# CH340BRIDGE_CONVERTER.net
KiCad netlist of a schematic drawn in EAGLE
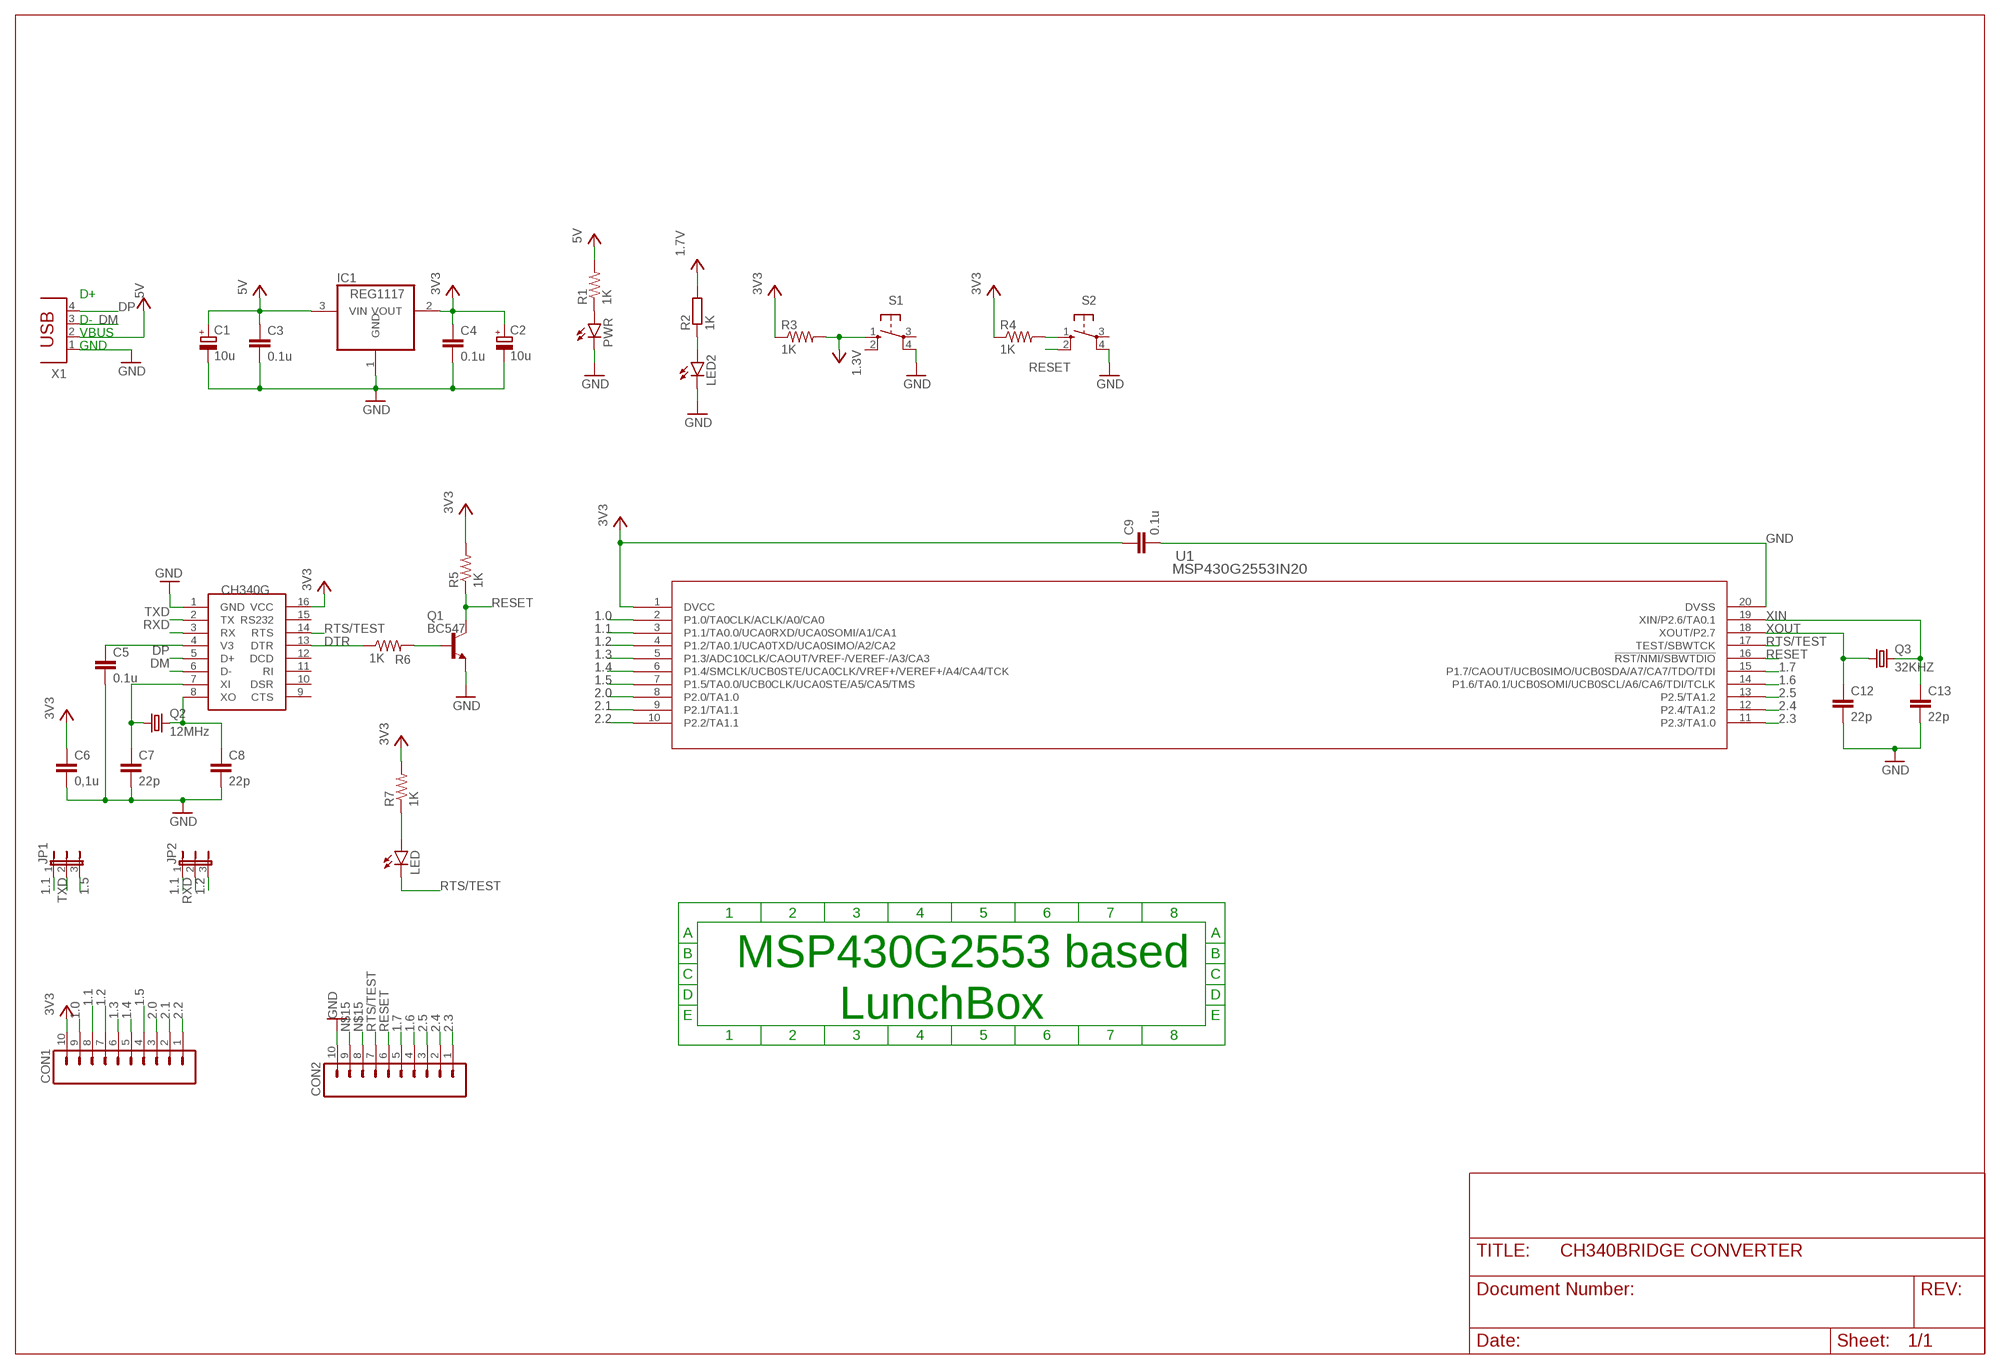
[diagram p0: schematic, sheet 1]

(export (version "E")
  (design (tool "Eeschema 10.0.6"))
  (components
    (comp (ref "C1")
      (value "10u")
      (footprint "eagle-import:TT5D7")
      (libsource (lib "eagle-import") (part "CPOL-EUTT5D7"))
    )
    (comp (ref "C2")
      (value "10u")
      (footprint "eagle-import:TT5D7")
      (libsource (lib "eagle-import") (part "CPOL-EUTT5D7"))
    )
    (comp (ref "C3")
      (value "0.1u")
      (footprint "eagle-import:C025-025X050")
      (libsource (lib "eagle-import") (part "C-EU025-025X050"))
    )
    (comp (ref "C4")
      (value "0.1u")
      (footprint "eagle-import:C025-025X050")
      (libsource (lib "eagle-import") (part "C-EU025-025X050"))
    )
    (comp (ref "C5")
      (value "0.1u")
      (footprint "eagle-import:C0805")
      (libsource (lib "eagle-import") (part "C-EUC0805"))
    )
    (comp (ref "C6")
      (value "0,1u")
      (footprint "eagle-import:C0805")
      (libsource (lib "eagle-import") (part "C-EUC0805"))
    )
    (comp (ref "C7")
      (value "22p")
      (footprint "eagle-import:C0805")
      (libsource (lib "eagle-import") (part "C-EUC0805"))
    )
    (comp (ref "C8")
      (value "22p")
      (footprint "eagle-import:C0805")
      (libsource (lib "eagle-import") (part "C-EUC0805"))
    )
    (comp (ref "C9")
      (value "0.1u")
      (footprint "eagle-import:C075-032X103")
      (libsource (lib "eagle-import") (part "C-EU075-032X103"))
    )
    (comp (ref "C12")
      (value "22p")
      (footprint "eagle-import:C0805")
      (libsource (lib "eagle-import") (part "C-EUC0805"))
    )
    (comp (ref "C13")
      (value "22p")
      (footprint "eagle-import:C0805")
      (libsource (lib "eagle-import") (part "C-EUC0805"))
    )
    (comp (ref "CON1")
      (value "M10")
      (footprint "eagle-import:10P")
      (fields (field (name "SPICEPREFIX") "C"))
      (libsource (lib "eagle-import") (part "M10"))
    )
    (comp (ref "CON2")
      (value "M10")
      (footprint "eagle-import:10P")
      (libsource (lib "eagle-import") (part "M10"))
    )
    (comp (ref "IC1")
      (value "REG1117")
      (footprint "eagle-import:SOT223")
      (libsource (lib "eagle-import") (part "REG1117"))
    )
    (comp (ref "JP1")
      (value "JP2E")
      (footprint "eagle-import:JP2")
      (libsource (lib "eagle-import") (part "JP2E"))
    )
    (comp (ref "JP2")
      (value "JP2E")
      (footprint "eagle-import:JP2")
      (libsource (lib "eagle-import") (part "JP2E"))
    )
    (comp (ref "LED")
      (value "LED3MM")
      (footprint "eagle-import:LED3MM")
      (libsource (lib "eagle-import") (part "LED3MM"))
    )
    (comp (ref "LED2")
      (value "LED3MM")
      (footprint "eagle-import:LED3MM")
      (libsource (lib "eagle-import") (part "LED3MM"))
    )
    (comp (ref "PWR")
      (value "LED3MM")
      (footprint "eagle-import:LED3MM")
      (libsource (lib "eagle-import") (part "LED3MM"))
    )
    (comp (ref "Q1")
      (value "BC547")
      (footprint "eagle-import:TO92")
      (libsource (lib "eagle-import") (part "BC547"))
    )
    (comp (ref "Q2")
      (value "12MHz")
      (footprint "eagle-import:HC49_S")
      (libsource (lib "eagle-import") (part "CRYSTALHC49S"))
    )
    (comp (ref "Q3")
      (value "32KHZ")
      (footprint "eagle-import:TC26H")
      (libsource (lib "eagle-import") (part "CRYSTALTC26H"))
    )
    (comp (ref "R1")
      (value "1K")
      (footprint "eagle-import:0207_10")
      (libsource (lib "eagle-import") (part "R-US_0207/10"))
    )
    (comp (ref "R2")
      (value "1K")
      (footprint "eagle-import:0207_12")
      (libsource (lib "eagle-import") (part "R-EU_0207/12"))
    )
    (comp (ref "R3")
      (value "1K")
      (footprint "eagle-import:0204_7")
      (libsource (lib "eagle-import") (part "R-US_0204/7"))
    )
    (comp (ref "R4")
      (value "1K")
      (footprint "eagle-import:0204_7")
      (libsource (lib "eagle-import") (part "R-US_0204/7"))
    )
    (comp (ref "R5")
      (value "1K")
      (footprint "eagle-import:0207_10")
      (libsource (lib "eagle-import") (part "R-US_0207/10"))
    )
    (comp (ref "R6")
      (value "1K")
      (footprint "eagle-import:0207_10")
      (libsource (lib "eagle-import") (part "R-US_0207/10"))
    )
    (comp (ref "R7")
      (value "1K")
      (footprint "eagle-import:0207_10")
      (libsource (lib "eagle-import") (part "R-US_0207/10"))
    )
    (comp (ref "S1")
      (value "10-XX")
      (footprint "eagle-import:B3F-10XX")
      (fields (field (name "MPN") "B3F-1000"))
      (libsource (lib "eagle-import") (part "10-XX"))
    )
    (comp (ref "S2")
      (value "10-XX")
      (footprint "eagle-import:B3F-10XX")
      (fields (field (name "MPN") "B3F-1000"))
      (libsource (lib "eagle-import") (part "10-XX"))
    )
    (comp (ref "U$1")
      (value "CH340G")
      (footprint "eagle-import:SOIC16")
      (libsource (lib "eagle-import") (part "CH340G"))
    )
    (comp (ref "U1")
      (value "MSP430G2553IN20")
      (footprint "eagle-import:N20_TEX")
      (fields (field (name "COPYRIGHT") "Copyright (C) 2024 Ultra Librarian. All rights reserved."))
      (libsource (lib "eagle-import") (part "MSP430G2553IN20"))
    )
    (comp (ref "X1")
      (value "PN87520")
      (footprint "eagle-import:PN87520")
      (libsource (lib "eagle-import") (part "PN87520"))
    )
  )
  (nets
    (net (code "1") (name "/1.0") (class "Default")
      (node (ref "CON1") (pin "9") (pinfunction "9_9") (pintype "passive"))
      (node (ref "U1") (pin "2") (pinfunction "P1.0/TA0CLK/ACLK/A0/CA0_2") (pintype "bidirectional"))
    )
    (net (code "2") (name "/1.1") (class "Default")
      (node (ref "CON1") (pin "8") (pinfunction "8_8") (pintype "passive"))
      (node (ref "JP1") (pin "1") (pinfunction "1_1") (pintype "passive"))
      (node (ref "JP2") (pin "1") (pinfunction "1_1") (pintype "passive"))
      (node (ref "U1") (pin "3") (pinfunction "P1.1/TA0.0/UCA0RXD/UCA0SOMI/A1/CA1_3") (pintype "bidirectional"))
    )
    (net (code "3") (name "/1.2") (class "Default")
      (node (ref "CON1") (pin "7") (pinfunction "7_7") (pintype "passive"))
      (node (ref "JP2") (pin "3") (pinfunction "3_3") (pintype "passive"))
      (node (ref "U1") (pin "4") (pinfunction "P1.2/TA0.1/UCA0TXD/UCA0SIMO/A2/CA2_4") (pintype "bidirectional"))
    )
    (net (code "4") (name "/1.3") (class "Default")
      (node (ref "CON1") (pin "6") (pinfunction "6_6") (pintype "passive"))
      (node (ref "U1") (pin "5") (pinfunction "P1.3/ADC10CLK/CAOUT/VREF-/VEREF-/A3/CA3_5") (pintype "bidirectional"))
    )
    (net (code "5") (name "/1.4") (class "Default")
      (node (ref "CON1") (pin "5") (pinfunction "5_5") (pintype "passive"))
      (node (ref "U1") (pin "6") (pinfunction "P1.4/SMCLK/UCB0STE/UCA0CLK/VREF+/VEREF+/A4/CA4/TCK_6") (pintype "bidirectional"))
    )
    (net (code "6") (name "/1.5") (class "Default")
      (node (ref "CON1") (pin "4") (pinfunction "4_4") (pintype "passive"))
      (node (ref "JP1") (pin "3") (pinfunction "3_3") (pintype "passive"))
      (node (ref "U1") (pin "7") (pinfunction "P1.5/TA0.0/UCB0CLK/UCA0STE/A5/CA5/TMS_7") (pintype "bidirectional"))
    )
    (net (code "7") (name "/1.6") (class "Default")
      (node (ref "CON2") (pin "4") (pinfunction "4_4") (pintype "passive"))
      (node (ref "U1") (pin "14") (pinfunction "P1.6/TA0.1/UCB0SOMI/UCB0SCL/A6/CA6/TDI/TCLK_14") (pintype "bidirectional"))
    )
    (net (code "8") (name "/1.7") (class "Default")
      (node (ref "CON2") (pin "5") (pinfunction "5_5") (pintype "passive"))
      (node (ref "U1") (pin "15") (pinfunction "P1.7/CAOUT/UCB0SIMO/UCB0SDA/A7/CA7/TDO/TDI_15") (pintype "bidirectional"))
    )
    (net (code "9") (name "/2.0") (class "Default")
      (node (ref "CON1") (pin "3") (pinfunction "3_3") (pintype "passive"))
      (node (ref "U1") (pin "8") (pinfunction "P2.0/TA1.0_8") (pintype "bidirectional"))
    )
    (net (code "10") (name "/2.1") (class "Default")
      (node (ref "CON1") (pin "2") (pinfunction "2_2") (pintype "passive"))
      (node (ref "U1") (pin "9") (pinfunction "P2.1/TA1.1_9") (pintype "bidirectional"))
    )
    (net (code "11") (name "/2.2") (class "Default")
      (node (ref "CON1") (pin "1") (pinfunction "1_1") (pintype "passive"))
      (node (ref "U1") (pin "10") (pinfunction "P2.2/TA1.1_10") (pintype "bidirectional"))
    )
    (net (code "12") (name "/2.3") (class "Default")
      (node (ref "CON2") (pin "1") (pinfunction "1_1") (pintype "passive"))
      (node (ref "U1") (pin "11") (pinfunction "P2.3/TA1.0_11") (pintype "bidirectional"))
    )
    (net (code "13") (name "/2.4") (class "Default")
      (node (ref "CON2") (pin "2") (pinfunction "2_2") (pintype "passive"))
      (node (ref "U1") (pin "12") (pinfunction "P2.4/TA1.2_12") (pintype "bidirectional"))
    )
    (net (code "14") (name "/2.5") (class "Default")
      (node (ref "CON2") (pin "3") (pinfunction "3_3") (pintype "passive"))
      (node (ref "U1") (pin "13") (pinfunction "P2.5/TA1.2_13") (pintype "bidirectional"))
    )
    (net (code "15") (name "/DM") (class "Default")
      (node (ref "U$1") (pin "6") (pinfunction "D-_6") (pintype "bidirectional"))
      (node (ref "X1") (pin "3") (pinfunction "3_3") (pintype "passive"))
    )
    (net (code "16") (name "/DP") (class "Default")
      (node (ref "U$1") (pin "5") (pinfunction "D+_5") (pintype "bidirectional"))
      (node (ref "X1") (pin "4") (pinfunction "4_4") (pintype "passive"))
    )
    (net (code "17") (name "/DTR") (class "Default")
      (node (ref "R6") (pin "1") (pinfunction "1_1") (pintype "passive"))
      (node (ref "U$1") (pin "13") (pinfunction "DTR_13") (pintype "bidirectional"))
    )
    (net (code "18") (name "/N$15") (class "Default")
      (node (ref "CON2") (pin "8") (pinfunction "8_8") (pintype "passive"))
      (node (ref "CON2") (pin "9") (pinfunction "9_9") (pintype "passive"))
    )
    (net (code "19") (name "/RESET") (class "Default")
      (node (ref "CON2") (pin "6") (pinfunction "6_6") (pintype "passive"))
      (node (ref "Q1") (pin "3") (pinfunction "C_3") (pintype "passive"))
      (node (ref "R5") (pin "1") (pinfunction "1_1") (pintype "passive"))
      (node (ref "S2") (pin "2") (pinfunction "S1_2") (pintype "passive"))
      (node (ref "U1") (pin "16") (pinfunction "~{RST/NMI/SBWTDIO}_16") (pintype "bidirectional"))
    )
    (net (code "20") (name "/RTS{slash}TEST") (class "Default")
      (node (ref "CON2") (pin "7") (pinfunction "7_7") (pintype "passive"))
      (node (ref "LED") (pin "K") (pinfunction "C_K") (pintype "passive"))
      (node (ref "U$1") (pin "14") (pinfunction "RTS_14") (pintype "bidirectional"))
      (node (ref "U1") (pin "17") (pinfunction "TEST/SBWTCK_17") (pintype "bidirectional"))
    )
    (net (code "21") (name "/RXD") (class "Default")
      (node (ref "JP2") (pin "2") (pinfunction "2_2") (pintype "passive"))
      (node (ref "U$1") (pin "3") (pinfunction "RX_3") (pintype "bidirectional"))
    )
    (net (code "22") (name "/TXD") (class "Default")
      (node (ref "JP1") (pin "2") (pinfunction "2_2") (pintype "passive"))
      (node (ref "U$1") (pin "2") (pinfunction "TX_2") (pintype "bidirectional"))
    )
    (net (code "23") (name "/XIN") (class "Default")
      (node (ref "C13") (pin "1") (pinfunction "1_1") (pintype "passive"))
      (node (ref "Q3") (pin "2") (pinfunction "2_2") (pintype "passive"))
      (node (ref "U1") (pin "19") (pinfunction "XIN/P2.6/TA0.1_19") (pintype "bidirectional"))
    )
    (net (code "24") (name "/XOUT") (class "Default")
      (node (ref "C12") (pin "1") (pinfunction "1_1") (pintype "passive"))
      (node (ref "Q3") (pin "1") (pinfunction "1_1") (pintype "passive"))
      (node (ref "U1") (pin "18") (pinfunction "XOUT/P2.7_18") (pintype "bidirectional"))
    )
    (net (code "25") (name "1.3V") (class "Default")
      (node (ref "C1") (pin "+") (pinfunction "+_+") (pintype "passive"))
      (node (ref "C2") (pin "+") (pinfunction "+_+") (pintype "passive"))
      (node (ref "C3") (pin "1") (pinfunction "1_1") (pintype "passive"))
      (node (ref "C4") (pin "1") (pinfunction "1_1") (pintype "passive"))
      (node (ref "C6") (pin "1") (pinfunction "1_1") (pintype "passive"))
      (node (ref "C9") (pin "1") (pinfunction "1_1") (pintype "passive"))
      (node (ref "CON1") (pin "10") (pinfunction "10_10") (pintype "passive"))
      (node (ref "IC1") (pin "2") (pinfunction "VOUT_2") (pintype "output"))
      (node (ref "IC1") (pin "3") (pinfunction "VIN_3") (pintype "input"))
      (node (ref "R1") (pin "2") (pinfunction "2_2") (pintype "passive"))
      (node (ref "R2") (pin "2") (pinfunction "2_2") (pintype "passive"))
      (node (ref "R3") (pin "1") (pinfunction "1_1") (pintype "passive"))
      (node (ref "R3") (pin "2") (pinfunction "2_2") (pintype "passive"))
      (node (ref "R4") (pin "1") (pinfunction "1_1") (pintype "passive"))
      (node (ref "R5") (pin "2") (pinfunction "2_2") (pintype "passive"))
      (node (ref "R7") (pin "2") (pinfunction "2_2") (pintype "passive"))
      (node (ref "S1") (pin "1") (pinfunction "S_1") (pintype "passive"))
      (node (ref "U$1") (pin "16") (pinfunction "VCC_16") (pintype "bidirectional"))
      (node (ref "U1") (pin "1") (pinfunction "DVCC_1") (pintype "power_in"))
      (node (ref "X1") (pin "2") (pinfunction "2_2") (pintype "passive"))
    )
    (net (code "26") (name "GND") (class "Default")
      (node (ref "C1") (pin "-") (pinfunction "-_-") (pintype "passive"))
      (node (ref "C12") (pin "2") (pinfunction "2_2") (pintype "passive"))
      (node (ref "C13") (pin "2") (pinfunction "2_2") (pintype "passive"))
      (node (ref "C2") (pin "-") (pinfunction "-_-") (pintype "passive"))
      (node (ref "C3") (pin "2") (pinfunction "2_2") (pintype "passive"))
      (node (ref "C4") (pin "2") (pinfunction "2_2") (pintype "passive"))
      (node (ref "C5") (pin "2") (pinfunction "2_2") (pintype "passive"))
      (node (ref "C6") (pin "2") (pinfunction "2_2") (pintype "passive"))
      (node (ref "C7") (pin "2") (pinfunction "2_2") (pintype "passive"))
      (node (ref "C8") (pin "2") (pinfunction "2_2") (pintype "passive"))
      (node (ref "C9") (pin "2") (pinfunction "2_2") (pintype "passive"))
      (node (ref "CON2") (pin "10") (pinfunction "10_10") (pintype "passive"))
      (node (ref "IC1") (pin "1") (pinfunction "GND_1") (pintype "power_in"))
      (node (ref "LED2") (pin "K") (pinfunction "C_K") (pintype "passive"))
      (node (ref "PWR") (pin "K") (pinfunction "C_K") (pintype "passive"))
      (node (ref "Q1") (pin "1") (pinfunction "E_1") (pintype "passive"))
      (node (ref "S1") (pin "4") (pinfunction "P1_4") (pintype "passive"))
      (node (ref "S2") (pin "4") (pinfunction "P1_4") (pintype "passive"))
      (node (ref "U$1") (pin "1") (pinfunction "GND_1") (pintype "bidirectional"))
      (node (ref "U1") (pin "20") (pinfunction "DVSS_20") (pintype "power_in"))
      (node (ref "X1") (pin "1") (pinfunction "1_1") (pintype "passive"))
    )
    (net (code "27") (name "Net-(LED-PadA)") (class "Default")
      (node (ref "LED") (pin "A") (pinfunction "A_A") (pintype "passive"))
      (node (ref "R7") (pin "1") (pinfunction "1_1") (pintype "passive"))
    )
    (net (code "28") (name "Net-(LED2-PadA)") (class "Default")
      (node (ref "LED2") (pin "A") (pinfunction "A_A") (pintype "passive"))
      (node (ref "R2") (pin "1") (pinfunction "1_1") (pintype "passive"))
    )
    (net (code "29") (name "Net-(PWR-PadA)") (class "Default")
      (node (ref "PWR") (pin "A") (pinfunction "A_A") (pintype "passive"))
      (node (ref "R1") (pin "1") (pinfunction "1_1") (pintype "passive"))
    )
    (net (code "30") (name "Net-(Q1-B)") (class "Default")
      (node (ref "Q1") (pin "2") (pinfunction "B_2") (pintype "passive"))
      (node (ref "R6") (pin "2") (pinfunction "2_2") (pintype "passive"))
    )
    (net (code "31") (name "Net-(S2-S)") (class "Default")
      (node (ref "R4") (pin "2") (pinfunction "2_2") (pintype "passive"))
      (node (ref "S2") (pin "1") (pinfunction "S_1") (pintype "passive"))
    )
    (net (code "32") (name "Net-(U$1-V3)") (class "Default")
      (node (ref "C5") (pin "1") (pinfunction "1_1") (pintype "passive"))
      (node (ref "U$1") (pin "4") (pinfunction "V3_4") (pintype "bidirectional"))
    )
    (net (code "33") (name "Net-(U$1-XI)") (class "Default")
      (node (ref "C7") (pin "1") (pinfunction "1_1") (pintype "passive"))
      (node (ref "Q2") (pin "1") (pinfunction "1_1") (pintype "passive"))
      (node (ref "U$1") (pin "7") (pinfunction "XI_7") (pintype "bidirectional"))
    )
    (net (code "34") (name "Net-(U$1-XO)") (class "Default")
      (node (ref "C8") (pin "1") (pinfunction "1_1") (pintype "passive"))
      (node (ref "Q2") (pin "2") (pinfunction "2_2") (pintype "passive"))
      (node (ref "U$1") (pin "8") (pinfunction "XO_8") (pintype "bidirectional"))
    )
    (net (code "35") (name "unconnected-(S1-P-Pad3)") (class "Default")
      (node (ref "S1") (pin "3") (pinfunction "P_3") (pintype "passive"))
    )
    (net (code "36") (name "unconnected-(S1-S1-Pad2)") (class "Default")
      (node (ref "S1") (pin "2") (pinfunction "S1_2") (pintype "passive"))
    )
    (net (code "37") (name "unconnected-(S2-P-Pad3)") (class "Default")
      (node (ref "S2") (pin "3") (pinfunction "P_3") (pintype "passive"))
    )
    (net (code "38") (name "unconnected-(U$1-CTS-Pad9)") (class "Default")
      (node (ref "U$1") (pin "9") (pinfunction "CTS_9") (pintype "bidirectional"))
    )
    (net (code "39") (name "unconnected-(U$1-DCD-Pad12)") (class "Default")
      (node (ref "U$1") (pin "12") (pinfunction "DCD_12") (pintype "bidirectional"))
    )
    (net (code "40") (name "unconnected-(U$1-DSR-Pad10)") (class "Default")
      (node (ref "U$1") (pin "10") (pinfunction "DSR_10") (pintype "bidirectional"))
    )
    (net (code "41") (name "unconnected-(U$1-RI-Pad11)") (class "Default")
      (node (ref "U$1") (pin "11") (pinfunction "RI_11") (pintype "bidirectional"))
    )
    (net (code "42") (name "unconnected-(U$1-RS232-Pad15)") (class "Default")
      (node (ref "U$1") (pin "15") (pinfunction "RS232_15") (pintype "bidirectional"))
    )
  )
)
